# main2.net
KiCad netlist of a schematic drawn in EAGLE
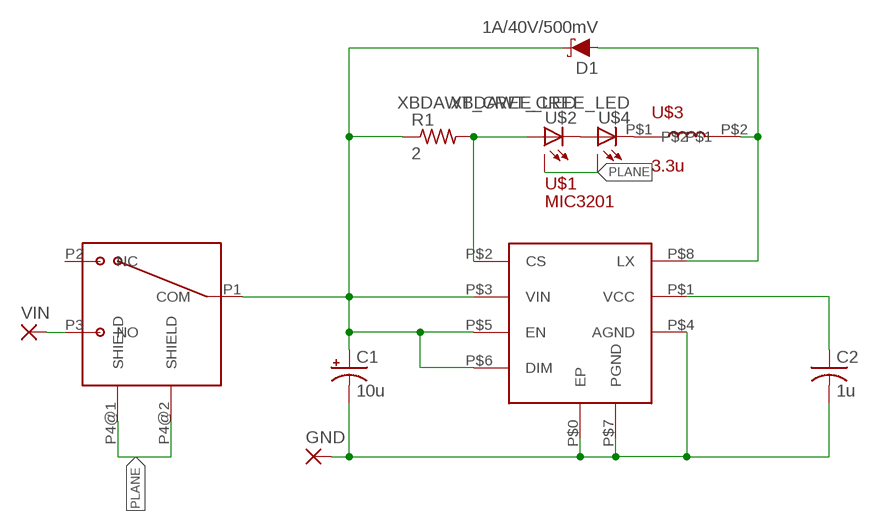
[diagram p0: schematic, sheet 1]

(export (version "E")
  (design (tool "Eeschema 10.0.6"))
  (components
    (comp (ref "C1")
      (value "10u")
      (footprint "eagle-import:E2-5")
      (libsource (lib "eagle-import") (part "CPOL-USE2-5"))
    )
    (comp (ref "C2")
      (value "1u")
      (footprint "eagle-import:C0603K")
      (libsource (lib "eagle-import") (part "C-USC0603K"))
    )
    (comp (ref "D1")
      (value "1A/40V/500mV")
      (footprint "eagle-import:SMA-DIODE")
      (libsource (lib "eagle-import") (part "DIODE-SCHOTTKY-SS14"))
    )
    (comp (ref "GND")
      (value "2,54/1,0")
      (footprint "eagle-import:2,54_1,0")
      (libsource (lib "eagle-import") (part "2,54/1,0"))
    )
    (comp (ref "R1")
      (value "2")
      (footprint "eagle-import:R0603")
      (libsource (lib "eagle-import") (part "R-US_R0603"))
    )
    (comp (ref "U$1")
      (value "MIC3201")
      (footprint "eagle-import:SOICNEP-8LD-LP-1")
      (libsource (lib "eagle-import") (part "MIC3201"))
    )
    (comp (ref "U$2")
      (value "XBDAWT_CREE_LED")
      (footprint "eagle-import:XBDAWT")
      (libsource (lib "eagle-import") (part "XBDAWT_CREE_LED"))
    )
    (comp (ref "U$3")
      (value "3.3u")
      (footprint "eagle-import:DO1813H")
      (libsource (lib "eagle-import") (part "DO1813H"))
    )
    (comp (ref "U$4")
      (value "XBDAWT_CREE_LED")
      (footprint "eagle-import:XBDAWT")
      (libsource (lib "eagle-import") (part "XBDAWT_CREE_LED"))
    )
    (comp (ref "U$5")
      (value "SS312")
      (footprint "eagle-import:SS312")
      (libsource (lib "eagle-import") (part "SS312"))
    )
    (comp (ref "VIN")
      (value "2,54/1,0")
      (footprint "eagle-import:2,54_1,0")
      (fields (field (name "SPICEPREFIX") "X"))
      (libsource (lib "eagle-import") (part "2,54/1,0"))
    )
  )
  (nets
    (net (code "1") (name "Net-(GND-P)") (class "Default")
      (node (ref "C1") (pin "-") (pinfunction "-_-") (pintype "passive"))
      (node (ref "C2") (pin "2") (pinfunction "2_2") (pintype "passive"))
      (node (ref "GND") (pin "1") (pinfunction "P_1") (pintype "passive"))
      (node (ref "U$1") (pin "P$0") (pinfunction "EP_P$0") (pintype "bidirectional"))
      (node (ref "U$1") (pin "P$4") (pinfunction "AGND_P$4") (pintype "bidirectional"))
      (node (ref "U$1") (pin "P$7") (pinfunction "PGND_P$7") (pintype "bidirectional"))
    )
    (net (code "2") (name "Net-(U$1-CS)") (class "Default")
      (node (ref "R1") (pin "2") (pinfunction "2_2") (pintype "passive"))
      (node (ref "U$1") (pin "P$2") (pinfunction "CS_P$2") (pintype "bidirectional"))
      (node (ref "U$2") (pin "P$2") (pinfunction "A_P$2") (pintype "passive"))
    )
    (net (code "3") (name "Net-(U$1-DIM)") (class "Default")
      (node (ref "C1") (pin "+") (pinfunction "+_+") (pintype "passive"))
      (node (ref "D1") (pin "C") (pinfunction "C_C") (pintype "passive"))
      (node (ref "R1") (pin "1") (pinfunction "1_1") (pintype "passive"))
      (node (ref "U$1") (pin "P$3") (pinfunction "VIN_P$3") (pintype "bidirectional"))
      (node (ref "U$1") (pin "P$5") (pinfunction "EN_P$5") (pintype "bidirectional"))
      (node (ref "U$1") (pin "P$6") (pinfunction "DIM_P$6") (pintype "bidirectional"))
      (node (ref "U$5") (pin "P1") (pinfunction "COM_P1") (pintype "bidirectional"))
    )
    (net (code "4") (name "Net-(U$1-LX)") (class "Default")
      (node (ref "D1") (pin "A") (pinfunction "A_A") (pintype "passive"))
      (node (ref "U$1") (pin "P$8") (pinfunction "LX_P$8") (pintype "bidirectional"))
      (node (ref "U$3") (pin "P$2") (pinfunction "P$2_P$2") (pintype "bidirectional"))
    )
    (net (code "5") (name "Net-(U$1-VCC)") (class "Default")
      (node (ref "C2") (pin "1") (pinfunction "1_1") (pintype "passive"))
      (node (ref "U$1") (pin "P$1") (pinfunction "VCC_P$1") (pintype "bidirectional"))
    )
    (net (code "6") (name "Net-(U$2-C)") (class "Default")
      (node (ref "U$2") (pin "P$3") (pinfunction "C_P$3") (pintype "passive"))
      (node (ref "U$4") (pin "P$2") (pinfunction "A_P$2") (pintype "passive"))
    )
    (net (code "7") (name "Net-(U$4-C)") (class "Default")
      (node (ref "U$3") (pin "P$1") (pinfunction "P$1_P$1") (pintype "bidirectional"))
      (node (ref "U$4") (pin "P$3") (pinfunction "C_P$3") (pintype "passive"))
    )
    (net (code "8") (name "Net-(U$5-NO)") (class "Default")
      (node (ref "U$5") (pin "P3") (pinfunction "NO_P3") (pintype "bidirectional"))
      (node (ref "VIN") (pin "1") (pinfunction "P_1") (pintype "passive"))
    )
    (net (code "9") (name "PLANE") (class "Default")
      (node (ref "U$2") (pin "P$1") (pinfunction "A1_P$1") (pintype "passive"))
      (node (ref "U$4") (pin "P$1") (pinfunction "A1_P$1") (pintype "passive"))
      (node (ref "U$5") (pin "P4@1") (pinfunction "SHIELD_P4@1") (pintype "bidirectional"))
      (node (ref "U$5") (pin "P4@2") (pinfunction "SHIELD_P4@2") (pintype "bidirectional"))
    )
    (net (code "10") (name "unconnected-(U$5-NC-PadP2)") (class "Default")
      (node (ref "U$5") (pin "P2") (pinfunction "NC_P2") (pintype "bidirectional"))
    )
  )
)
